# band-dsp-teensy.net
KiCad netlist of a schematic drawn in EAGLE
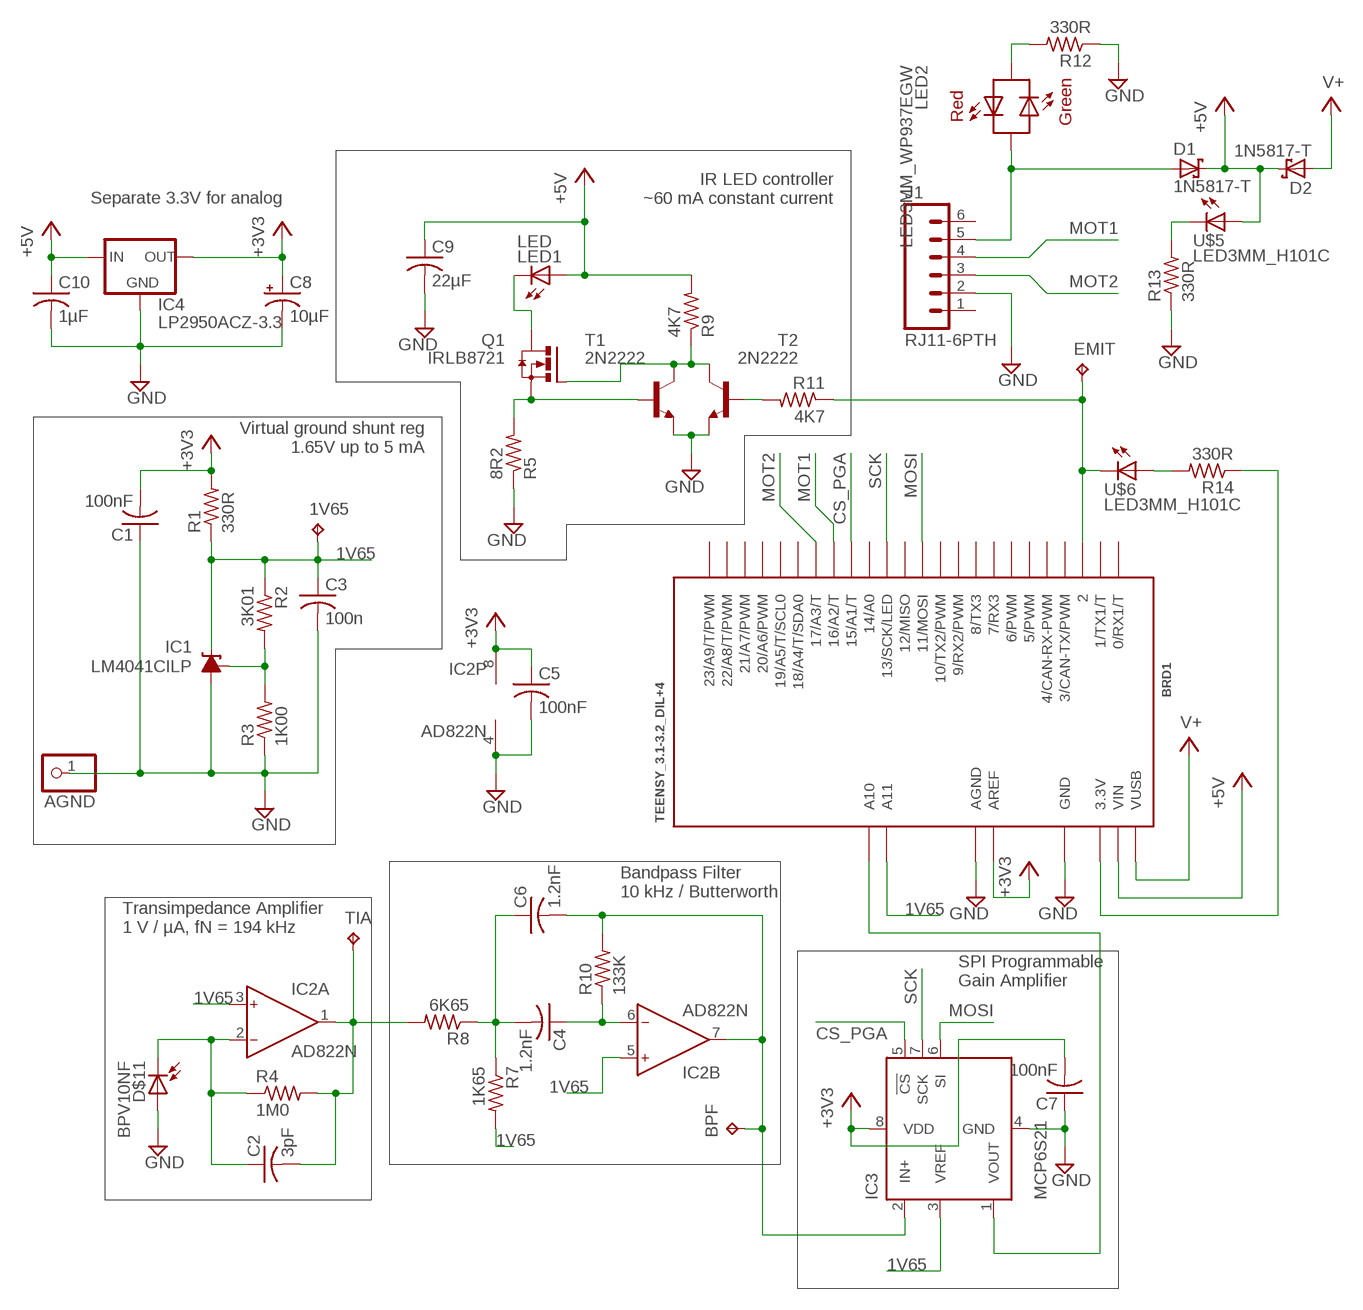
[diagram p0: schematic, sheet 1]

(export (version "E")
  (design (tool "Eeschema 10.0.6"))
  (components
    (comp (ref "1V65")
      (value "TPTP10R")
      (footprint "eagle-import:TP10R")
      (libsource (lib "eagle-import") (part "TPTP10R"))
    )
    (comp (ref "AGND")
      (value "PINHD-1X1")
      (footprint "eagle-import:1X01")
      (libsource (lib "eagle-import") (part "PINHD-1X1"))
    )
    (comp (ref "BPF")
      (value "TPTP10R")
      (footprint "eagle-import:TP10R")
      (libsource (lib "eagle-import") (part "TPTP10R"))
    )
    (comp (ref "BRD1")
      (value "TEENSY_3.1-3.2_DIL+4")
      (footprint "eagle-import:TEENSY_3.0-3.2&LC_DIL+4")
      (fields (field (name "MANF") "SparkFun Electronics"))
      (libsource (lib "eagle-import") (part "TEENSY_3.1-3.2_DIL+4"))
    )
    (comp (ref "C1")
      (value "100nF")
      (footprint "eagle-import:C025-025X050")
      (fields (field (name "MANF") "Vishay BC Components"))
      (libsource (lib "eagle-import") (part "C-US025-025X050"))
    )
    (comp (ref "C2")
      (value "3pF")
      (footprint "eagle-import:C025-024X044")
      (fields (field (name "MANF") "TDK Corporation"))
      (libsource (lib "eagle-import") (part "C-US025-024X044"))
    )
    (comp (ref "C3")
      (value "100n")
      (footprint "eagle-import:C025-025X050")
      (fields (field (name "MANF") "Vishay BC Components"))
      (libsource (lib "eagle-import") (part "C-US025-025X050"))
    )
    (comp (ref "C4")
      (value "1.2nF")
      (footprint "eagle-import:C025-025X050")
      (fields (field (name "MANF") "Vishay BC Components"))
      (libsource (lib "eagle-import") (part "C-US025-025X050"))
    )
    (comp (ref "C5")
      (value "100nF")
      (footprint "eagle-import:C025-025X050")
      (fields (field (name "MANF") "Vishay BC Components"))
      (libsource (lib "eagle-import") (part "C-US025-025X050"))
    )
    (comp (ref "C6")
      (value "1.2nF")
      (footprint "eagle-import:C025-025X050")
      (fields (field (name "MANF") "Vishay BC Components"))
      (libsource (lib "eagle-import") (part "C-US025-025X050"))
    )
    (comp (ref "C7")
      (value "100nF")
      (footprint "eagle-import:C025-025X050")
      (fields (field (name "MANF") "Vishay BC Components"))
      (libsource (lib "eagle-import") (part "C-US025-025X050"))
    )
    (comp (ref "C8")
      (value "10µF")
      (footprint "eagle-import:E2,5-5")
      (fields (field (name "MANF") "AVX Corporation"))
      (libsource (lib "eagle-import") (part "CPOL-USE2.5-5"))
    )
    (comp (ref "C9")
      (value "22µF")
      (footprint "eagle-import:C050-045X075")
      (fields (field (name "MANF") "TDK Corporation"))
      (libsource (lib "eagle-import") (part "C-US050-045X075"))
    )
    (comp (ref "C10")
      (value "1µF")
      (footprint "eagle-import:C025-030X050")
      (fields (field (name "MANF") "TDK Corporation"))
      (libsource (lib "eagle-import") (part "C-US025-030X050"))
    )
    (comp (ref "D$11")
      (value "BPV10NF")
      (footprint "eagle-import:LED5MM")
      (fields (field (name "MANF") "Vishay Semiconductor Opto Division"))
      (libsource (lib "eagle-import") (part "BPV10NF"))
    )
    (comp (ref "D1")
      (value "1N5817-T")
      (footprint "eagle-import:DO41-7.6")
      (fields (field (name "MANF") "Fairchild Semiconductor"))
      (libsource (lib "eagle-import") (part "1N5817-T"))
    )
    (comp (ref "D2")
      (value "1N5817-T")
      (footprint "eagle-import:DO41-7.6")
      (fields (field (name "MANF") "Fairchild Semiconductor"))
      (libsource (lib "eagle-import") (part "1N5817-T"))
    )
    (comp (ref "EMIT")
      (value "TPPAD1-13")
      (footprint "eagle-import:P1-13")
      (libsource (lib "eagle-import") (part "TPPAD1-13"))
    )
    (comp (ref "IC1")
      (value "LM4041CILP")
      (footprint "eagle-import:LP_O-PBCY-W3")
      (fields (field (name "MANF") "Texas Instruments"))
      (libsource (lib "eagle-import") (part "LM4041ILPC"))
    )
    (comp (ref "IC2")
      (value "AD822N")
      (footprint "eagle-import:DIL08")
      (fields
        (field (name "MANF") "Analog Devices Inc.")
        (field (name "DIGIKEY#") "AD823ANZ-ND")
        (field (name "MANF#") "AD823ANZ")
      )
      (libsource (lib "eagle-import") (part "AD822N"))
    )
    (comp (ref "IC3")
      (value "MCP6S21")
      (footprint "eagle-import:DIL08")
      (fields (field (name "MANF") "Microchip Technology"))
      (libsource (lib "eagle-import") (part "MCP6S21"))
    )
    (comp (ref "IC4")
      (value "LP2950ACZ-3.3")
      (footprint "eagle-import:TO92")
      (fields (field (name "MANF") "Texas Instruments"))
      (libsource (lib "eagle-import") (part "LP2950?ACZ-3.3"))
    )
    (comp (ref "J1")
      (value "RJ11-6PTH")
      (footprint "eagle-import:RJ11-6")
      (fields (field (name "MANF") "Assmann WSW Components"))
      (libsource (lib "eagle-import") (part "RJ11-6PTH"))
    )
    (comp (ref "LED1")
      (value "LED")
      (footprint "eagle-import:1X02_3.5MM")
      (fields (field (name "MANF") "OSRAM Opto Semiconductors Inc"))
      (libsource (lib "eagle-import") (part "1X02_3.5MM_LED"))
    )
    (comp (ref "LED2")
      (value "LED3MM_WP937EGW")
      (footprint "eagle-import:LED3MM_H101C_BICOL")
      (fields (field (name "MANF") "Kingbright"))
      (libsource (lib "eagle-import") (part "LED3MM_WP937EGW"))
    )
    (comp (ref "Q1")
      (value "IRLB8721")
      (footprint "eagle-import:TO220BH")
      (fields (field (name "MANF") "Infineon Technologies"))
      (libsource (lib "eagle-import") (part "IRLB8721HORIZONTAL"))
    )
    (comp (ref "R1")
      (value "330R")
      (footprint "eagle-import:0207_9")
      (fields (field (name "MANF") "Stackpole Electronics Inc."))
      (libsource (lib "eagle-import") (part "R-US_0207/9"))
    )
    (comp (ref "R2")
      (value "3K01")
      (footprint "eagle-import:0207_9")
      (fields (field (name "MANF") "Stackpole Electronics Inc."))
      (libsource (lib "eagle-import") (part "R-US_0207/9"))
    )
    (comp (ref "R3")
      (value "1K00")
      (footprint "eagle-import:0207_9")
      (fields (field (name "MANF") "Stackpole Electronics Inc."))
      (libsource (lib "eagle-import") (part "R-US_0207/9"))
    )
    (comp (ref "R4")
      (value "1M0")
      (footprint "eagle-import:0207_9")
      (fields (field (name "MANF") "Stackpole Electronics Inc"))
      (libsource (lib "eagle-import") (part "R-US_0207/9"))
    )
    (comp (ref "R5")
      (value "8R2")
      (footprint "eagle-import:0207_9")
      (fields (field (name "DIGIKEY#") "S8.2HCT-ND") (field (name "MANF") "Stackpole Electronics Inc."))
      (libsource (lib "eagle-import") (part "R-US_0207/9"))
    )
    (comp (ref "R7")
      (value "1K65")
      (footprint "eagle-import:0207_9")
      (fields (field (name "MANF") "Yageo"))
      (libsource (lib "eagle-import") (part "R-US_0207/9"))
    )
    (comp (ref "R8")
      (value "6K65")
      (footprint "eagle-import:0207_9")
      (fields (field (name "MANF") "Yageo"))
      (libsource (lib "eagle-import") (part "R-US_0207/9"))
    )
    (comp (ref "R9")
      (value "4K7")
      (footprint "eagle-import:0207_9")
      (fields (field (name "MANF") "Stackpole Electronics Inc"))
      (libsource (lib "eagle-import") (part "R-US_0207/9"))
    )
    (comp (ref "R10")
      (value "133K")
      (footprint "eagle-import:0207_9")
      (fields (field (name "MANF") "Yageo"))
      (libsource (lib "eagle-import") (part "R-US_0207/9"))
    )
    (comp (ref "R11")
      (value "4K7")
      (footprint "eagle-import:0207_9")
      (fields (field (name "MANF") "Stackpole Electronics Inc"))
      (libsource (lib "eagle-import") (part "R-US_0207/9"))
    )
    (comp (ref "R12")
      (value "330R")
      (footprint "eagle-import:0207_9")
      (fields (field (name "MANF") "Stackpole Electronics Inc."))
      (libsource (lib "eagle-import") (part "R-US_0207/9"))
    )
    (comp (ref "R13")
      (value "330R")
      (footprint "eagle-import:0207_9")
      (fields (field (name "MANF") "Stackpole Electronics Inc."))
      (libsource (lib "eagle-import") (part "R-US_0207/9"))
    )
    (comp (ref "R14")
      (value "330R")
      (footprint "eagle-import:0207_9")
      (fields (field (name "MANF") "Stackpole Electronics Inc."))
      (libsource (lib "eagle-import") (part "R-US_0207/9"))
    )
    (comp (ref "T1")
      (value "2N2222")
      (footprint "eagle-import:TO92-EBC-OVAL")
      (fields (field (name "MANF") "Fairchild Semiconductor"))
      (libsource (lib "eagle-import") (part "2N2222"))
    )
    (comp (ref "T2")
      (value "2N2222")
      (footprint "eagle-import:TO92-EBC-OVAL")
      (fields (field (name "MANF") "Fairchild Semiconductor"))
      (libsource (lib "eagle-import") (part "2N2222"))
    )
    (comp (ref "TIA")
      (value "TPTP10R")
      (footprint "eagle-import:TP10R")
      (libsource (lib "eagle-import") (part "TPTP10R"))
    )
    (comp (ref "U$5")
      (value "LED3MM_H101C")
      (footprint "eagle-import:LED3MM_H101C")
      (fields (field (name "MANF") "Kingbright"))
      (libsource (lib "eagle-import") (part "LED3MM_H101C"))
    )
    (comp (ref "U$6")
      (value "LED3MM_H101C")
      (footprint "eagle-import:LED3MM_H101C")
      (fields (field (name "MANF") "Kingbright"))
      (libsource (lib "eagle-import") (part "LED3MM_H101C"))
    )
  )
  (nets
    (net (code "1") (name "+3V3") (class "Default")
      (node (ref "BRD1") (pin "AREF") (pinfunction "AREF_AREF") (pintype "power_in"))
      (node (ref "C1") (pin "2") (pinfunction "2_2") (pintype "passive"))
      (node (ref "C5") (pin "1") (pinfunction "1_1") (pintype "passive"))
      (node (ref "C7") (pin "2") (pinfunction "2_2") (pintype "passive"))
      (node (ref "C8") (pin "+") (pinfunction "+_+") (pintype "passive"))
      (node (ref "IC2") (pin "8") (pinfunction "V+_8") (pintype "power_in"))
      (node (ref "IC3") (pin "8") (pinfunction "VDD_8") (pintype "power_in"))
      (node (ref "IC4") (pin "1") (pinfunction "OUT_1") (pintype "passive"))
      (node (ref "R1") (pin "2") (pinfunction "2_2") (pintype "passive"))
    )
    (net (code "2") (name "+5V") (class "Default")
      (node (ref "BRD1") (pin "VIN") (pinfunction "VIN_VIN") (pintype "power_in"))
      (node (ref "C10") (pin "1") (pinfunction "1_1") (pintype "passive"))
      (node (ref "C9") (pin "1") (pinfunction "1_1") (pintype "passive"))
      (node (ref "D1") (pin "C") (pinfunction "C_C") (pintype "passive"))
      (node (ref "D2") (pin "C") (pinfunction "C_C") (pintype "passive"))
      (node (ref "IC4") (pin "3") (pinfunction "IN_3") (pintype "input"))
      (node (ref "LED1") (pin "1A") (pinfunction "A_1A") (pintype "passive"))
      (node (ref "R9") (pin "2") (pinfunction "2_2") (pintype "passive"))
      (node (ref "U$5") (pin "A") (pinfunction "A_A") (pintype "passive"))
    )
    (net (code "3") (name "/1V65") (class "Default")
      (node (ref "1V65") (pin "TP") (pinfunction "TP_TP") (pintype "input"))
      (node (ref "BRD1") (pin "A11") (pinfunction "A11_A11") (pintype "bidirectional"))
      (node (ref "C3") (pin "1") (pinfunction "1_1") (pintype "passive"))
      (node (ref "IC1") (pin "2") (pinfunction "C_2") (pintype "passive"))
      (node (ref "IC2") (pin "3") (pinfunction "IN+_3") (pintype "input"))
      (node (ref "IC2") (pin "5") (pinfunction "IN+_5") (pintype "input"))
      (node (ref "IC3") (pin "3") (pinfunction "VREF_3") (pintype "input"))
      (node (ref "R1") (pin "1") (pinfunction "1_1") (pintype "passive"))
      (node (ref "R2") (pin "1") (pinfunction "1_1") (pintype "passive"))
      (node (ref "R7") (pin "2") (pinfunction "2_2") (pintype "passive"))
    )
    (net (code "4") (name "/CS_PGA") (class "Default")
      (node (ref "BRD1") (pin "15/A1") (pinfunction "15/A1/T_15/A1") (pintype "bidirectional"))
      (node (ref "IC3") (pin "5") (pinfunction "~{CS}_5") (pintype "input"))
    )
    (net (code "5") (name "/MOSI") (class "Default")
      (node (ref "BRD1") (pin "11") (pinfunction "11/MOSI_11") (pintype "bidirectional"))
      (node (ref "IC3") (pin "6") (pinfunction "SI_6") (pintype "input"))
    )
    (net (code "6") (name "/MOT1") (class "Default")
      (node (ref "BRD1") (pin "16/A2") (pinfunction "16/A2/T_16/A2") (pintype "bidirectional"))
      (node (ref "J1") (pin "4") (pinfunction "4_4") (pintype "passive"))
    )
    (net (code "7") (name "/MOT2") (class "Default")
      (node (ref "BRD1") (pin "17/A3") (pinfunction "17/A3/T_17/A3") (pintype "bidirectional"))
      (node (ref "J1") (pin "3") (pinfunction "3_3") (pintype "passive"))
    )
    (net (code "8") (name "/SCK") (class "Default")
      (node (ref "BRD1") (pin "13") (pinfunction "13/SCK/LED_13") (pintype "bidirectional"))
      (node (ref "IC3") (pin "7") (pinfunction "SCK_7") (pintype "input"))
    )
    (net (code "9") (name "GND") (class "Default")
      (node (ref "AGND") (pin "1") (pinfunction "1_1") (pintype "passive"))
      (node (ref "BRD1") (pin "AGND") (pinfunction "AGND_AGND") (pintype "power_in"))
      (node (ref "BRD1") (pin "GND") (pinfunction "GND_GND") (pintype "power_in"))
      (node (ref "C1") (pin "1") (pinfunction "1_1") (pintype "passive"))
      (node (ref "C10") (pin "2") (pinfunction "2_2") (pintype "passive"))
      (node (ref "C3") (pin "2") (pinfunction "2_2") (pintype "passive"))
      (node (ref "C5") (pin "2") (pinfunction "2_2") (pintype "passive"))
      (node (ref "C7") (pin "1") (pinfunction "1_1") (pintype "passive"))
      (node (ref "C8") (pin "-") (pinfunction "-_-") (pintype "passive"))
      (node (ref "C9") (pin "2") (pinfunction "2_2") (pintype "passive"))
      (node (ref "D$11") (pin "A") (pinfunction "A_A") (pintype "passive"))
      (node (ref "IC1") (pin "3") (pinfunction "A_3") (pintype "passive"))
      (node (ref "IC2") (pin "4") (pinfunction "V-_4") (pintype "power_in"))
      (node (ref "IC3") (pin "4") (pinfunction "GND_4") (pintype "power_in"))
      (node (ref "IC4") (pin "2") (pinfunction "GND_2") (pintype "input"))
      (node (ref "J1") (pin "2") (pinfunction "2_2") (pintype "passive"))
      (node (ref "R12") (pin "1") (pinfunction "1_1") (pintype "passive"))
      (node (ref "R13") (pin "1") (pinfunction "1_1") (pintype "passive"))
      (node (ref "R3") (pin "1") (pinfunction "1_1") (pintype "passive"))
      (node (ref "R5") (pin "1") (pinfunction "1_1") (pintype "passive"))
      (node (ref "T1") (pin "E") (pinfunction "E_E") (pintype "passive"))
      (node (ref "T2") (pin "E") (pinfunction "E_E") (pintype "passive"))
    )
    (net (code "10") (name "Net-(BRD1-Pad2)") (class "Default")
      (node (ref "BRD1") (pin "2") (pinfunction "2_2") (pintype "bidirectional"))
      (node (ref "EMIT") (pin "TP") (pinfunction "TP_TP") (pintype "input"))
      (node (ref "R11") (pin "1") (pinfunction "1_1") (pintype "passive"))
      (node (ref "U$6") (pin "K") (pinfunction "K_K") (pintype "passive"))
    )
    (net (code "11") (name "Net-(BRD1-Pad3.3V)") (class "Default")
      (node (ref "BRD1") (pin "3.3V") (pinfunction "3.3V_3.3V") (pintype "power_in"))
      (node (ref "R14") (pin "1") (pinfunction "1_1") (pintype "passive"))
    )
    (net (code "12") (name "Net-(C4-Pad2)") (class "Default")
      (node (ref "C4") (pin "2") (pinfunction "2_2") (pintype "passive"))
      (node (ref "C6") (pin "1") (pinfunction "1_1") (pintype "passive"))
      (node (ref "R7") (pin "1") (pinfunction "1_1") (pintype "passive"))
      (node (ref "R8") (pin "1") (pinfunction "1_1") (pintype "passive"))
    )
    (net (code "13") (name "Net-(IC1-FB)") (class "Default")
      (node (ref "IC1") (pin "1") (pinfunction "FB_1") (pintype "passive"))
      (node (ref "R2") (pin "2") (pinfunction "2_2") (pintype "passive"))
      (node (ref "R3") (pin "2") (pinfunction "2_2") (pintype "passive"))
    )
    (net (code "14") (name "Net-(IC2A-IN-)") (class "Default")
      (node (ref "C2") (pin "1") (pinfunction "1_1") (pintype "passive"))
      (node (ref "D$11") (pin "K") (pinfunction "K_K") (pintype "passive"))
      (node (ref "IC2") (pin "2") (pinfunction "IN-_2") (pintype "input"))
      (node (ref "R4") (pin "1") (pinfunction "1_1") (pintype "passive"))
    )
    (net (code "15") (name "Net-(IC2A-OUT)") (class "Default")
      (node (ref "C2") (pin "2") (pinfunction "2_2") (pintype "passive"))
      (node (ref "IC2") (pin "1") (pinfunction "OUT_1") (pintype "output"))
      (node (ref "R4") (pin "2") (pinfunction "2_2") (pintype "passive"))
      (node (ref "R8") (pin "2") (pinfunction "2_2") (pintype "passive"))
      (node (ref "TIA") (pin "TP") (pinfunction "TP_TP") (pintype "input"))
    )
    (net (code "16") (name "Net-(IC2B-IN-)") (class "Default")
      (node (ref "C4") (pin "1") (pinfunction "1_1") (pintype "passive"))
      (node (ref "IC2") (pin "6") (pinfunction "IN-_6") (pintype "input"))
      (node (ref "R10") (pin "1") (pinfunction "1_1") (pintype "passive"))
    )
    (net (code "17") (name "Net-(IC2B-OUT)") (class "Default")
      (node (ref "BPF") (pin "TP") (pinfunction "TP_TP") (pintype "input"))
      (node (ref "C6") (pin "2") (pinfunction "2_2") (pintype "passive"))
      (node (ref "IC2") (pin "7") (pinfunction "OUT_7") (pintype "output"))
      (node (ref "IC3") (pin "2") (pinfunction "IN+_2") (pintype "input"))
      (node (ref "R10") (pin "2") (pinfunction "2_2") (pintype "passive"))
    )
    (net (code "18") (name "Net-(IC3-VOUT)") (class "Default")
      (node (ref "BRD1") (pin "A10") (pinfunction "A10_A10") (pintype "bidirectional"))
      (node (ref "IC3") (pin "1") (pinfunction "VOUT_1") (pintype "output"))
    )
    (net (code "19") (name "Net-(LED1-K)") (class "Default")
      (node (ref "LED1") (pin "2K") (pinfunction "K_2K") (pintype "passive"))
      (node (ref "Q1") (pin "D") (pinfunction "D_D") (pintype "passive"))
    )
    (net (code "20") (name "Net-(LED2-GA)") (class "Default")
      (node (ref "D1") (pin "A") (pinfunction "A_A") (pintype "passive"))
      (node (ref "J1") (pin "5") (pinfunction "5_5") (pintype "passive"))
      (node (ref "LED2") (pin "SHORT") (pinfunction "GA_SHORT") (pintype "passive"))
    )
    (net (code "21") (name "Net-(LED2-GK)") (class "Default")
      (node (ref "LED2") (pin "LONG") (pinfunction "GK_LONG") (pintype "passive"))
      (node (ref "R12") (pin "2") (pinfunction "2_2") (pintype "passive"))
    )
    (net (code "22") (name "Net-(Q1-PadG)") (class "Default")
      (node (ref "Q1") (pin "G") (pinfunction "G_G") (pintype "passive"))
      (node (ref "R9") (pin "1") (pinfunction "1_1") (pintype "passive"))
      (node (ref "T1") (pin "C") (pinfunction "C_C") (pintype "passive"))
      (node (ref "T2") (pin "C") (pinfunction "C_C") (pintype "passive"))
    )
    (net (code "23") (name "Net-(Q1-PadS)") (class "Default")
      (node (ref "Q1") (pin "S") (pinfunction "S_S") (pintype "passive"))
      (node (ref "R5") (pin "2") (pinfunction "2_2") (pintype "passive"))
      (node (ref "T1") (pin "B") (pinfunction "B_B") (pintype "passive"))
    )
    (net (code "24") (name "Net-(R11-Pad2)") (class "Default")
      (node (ref "R11") (pin "2") (pinfunction "2_2") (pintype "passive"))
      (node (ref "T2") (pin "B") (pinfunction "B_B") (pintype "passive"))
    )
    (net (code "25") (name "Net-(R13-Pad2)") (class "Default")
      (node (ref "R13") (pin "2") (pinfunction "2_2") (pintype "passive"))
      (node (ref "U$5") (pin "K") (pinfunction "K_K") (pintype "passive"))
    )
    (net (code "26") (name "Net-(R14-Pad2)") (class "Default")
      (node (ref "R14") (pin "2") (pinfunction "2_2") (pintype "passive"))
      (node (ref "U$6") (pin "A") (pinfunction "A_A") (pintype "passive"))
    )
    (net (code "27") (name "V+") (class "Default")
      (node (ref "BRD1") (pin "VUSB") (pinfunction "VUSB_VUSB") (pintype "power_in"))
      (node (ref "D2") (pin "A") (pinfunction "A_A") (pintype "passive"))
    )
    (net (code "28") (name "unconnected-(BRD1-0{slash}RX1{slash}T-Pad0)") (class "Default")
      (node (ref "BRD1") (pin "0") (pinfunction "0/RX1/T_0") (pintype "bidirectional"))
    )
    (net (code "29") (name "unconnected-(BRD1-1{slash}TX1{slash}T-Pad1)") (class "Default")
      (node (ref "BRD1") (pin "1") (pinfunction "1/TX1/T_1") (pintype "bidirectional"))
    )
    (net (code "30") (name "unconnected-(BRD1-3{slash}CAN-TX{slash}PWM-Pad3)") (class "Default")
      (node (ref "BRD1") (pin "3") (pinfunction "3/CAN-TX/PWM_3") (pintype "bidirectional"))
    )
    (net (code "31") (name "unconnected-(BRD1-4{slash}CAN-RX-PWM-Pad4)") (class "Default")
      (node (ref "BRD1") (pin "4") (pinfunction "4/CAN-RX-PWM_4") (pintype "bidirectional"))
    )
    (net (code "32") (name "unconnected-(BRD1-5{slash}PWM-Pad5)") (class "Default")
      (node (ref "BRD1") (pin "5") (pinfunction "5/PWM_5") (pintype "bidirectional"))
    )
    (net (code "33") (name "unconnected-(BRD1-6{slash}PWM-Pad6)") (class "Default")
      (node (ref "BRD1") (pin "6") (pinfunction "6/PWM_6") (pintype "bidirectional"))
    )
    (net (code "34") (name "unconnected-(BRD1-7{slash}RX3-Pad7)") (class "Default")
      (node (ref "BRD1") (pin "7") (pinfunction "7/RX3_7") (pintype "bidirectional"))
    )
    (net (code "35") (name "unconnected-(BRD1-8{slash}TX3-Pad8)") (class "Default")
      (node (ref "BRD1") (pin "8") (pinfunction "8/TX3_8") (pintype "bidirectional"))
    )
    (net (code "36") (name "unconnected-(BRD1-9{slash}RX2{slash}PWM-Pad9)") (class "Default")
      (node (ref "BRD1") (pin "9") (pinfunction "9/RX2/PWM_9") (pintype "bidirectional"))
    )
    (net (code "37") (name "unconnected-(BRD1-10{slash}TX2{slash}PWM-Pad10)") (class "Default")
      (node (ref "BRD1") (pin "10") (pinfunction "10/TX2/PWM_10") (pintype "bidirectional"))
    )
    (net (code "38") (name "unconnected-(BRD1-12{slash}MISO-Pad12)") (class "Default")
      (node (ref "BRD1") (pin "12") (pinfunction "12/MISO_12") (pintype "bidirectional"))
    )
    (net (code "39") (name "unconnected-(BRD1-18{slash}A4{slash}T{slash}SDA0-Pad18{slash}A4)") (class "Default")
      (node (ref "BRD1") (pin "18/A4") (pinfunction "18/A4/T/SDA0_18/A4") (pintype "bidirectional"))
    )
    (net (code "40") (name "unconnected-(BRD1-19{slash}A5{slash}T{slash}SCL0-Pad19{slash}A5)") (class "Default")
      (node (ref "BRD1") (pin "19/A5") (pinfunction "19/A5/T/SCL0_19/A5") (pintype "bidirectional"))
    )
    (net (code "41") (name "unconnected-(BRD1-20{slash}A6{slash}PWM-Pad20{slash}A6)") (class "Default")
      (node (ref "BRD1") (pin "20/A6") (pinfunction "20/A6/PWM_20/A6") (pintype "bidirectional"))
    )
    (net (code "42") (name "unconnected-(BRD1-21{slash}A7{slash}PWM-Pad21{slash}A7)") (class "Default")
      (node (ref "BRD1") (pin "21/A7") (pinfunction "21/A7/PWM_21/A7") (pintype "bidirectional"))
    )
    (net (code "43") (name "unconnected-(BRD1-22{slash}A8{slash}T{slash}PWM-Pad22{slash}A8)") (class "Default")
      (node (ref "BRD1") (pin "22/A8") (pinfunction "22/A8/T/PWM_22/A8") (pintype "bidirectional"))
    )
    (net (code "44") (name "unconnected-(BRD1-23{slash}A9{slash}T{slash}PWM-Pad23{slash}A9)") (class "Default")
      (node (ref "BRD1") (pin "23/A9") (pinfunction "23/A9/T/PWM_23/A9") (pintype "bidirectional"))
    )
    (net (code "45") (name "unconnected-(BRD1-Pad14{slash}A0)") (class "Default")
      (node (ref "BRD1") (pin "14/A0") (pinfunction "14/A0_14/A0") (pintype "bidirectional"))
    )
    (net (code "46") (name "unconnected-(J1-Pad1)") (class "Default")
      (node (ref "J1") (pin "1") (pinfunction "1_1") (pintype "passive"))
    )
    (net (code "47") (name "unconnected-(J1-Pad6)") (class "Default")
      (node (ref "J1") (pin "6") (pinfunction "6_6") (pintype "passive"))
    )
  )
)
